# GRBL-Teknic.net
KiCad netlist of a schematic drawn in EAGLE
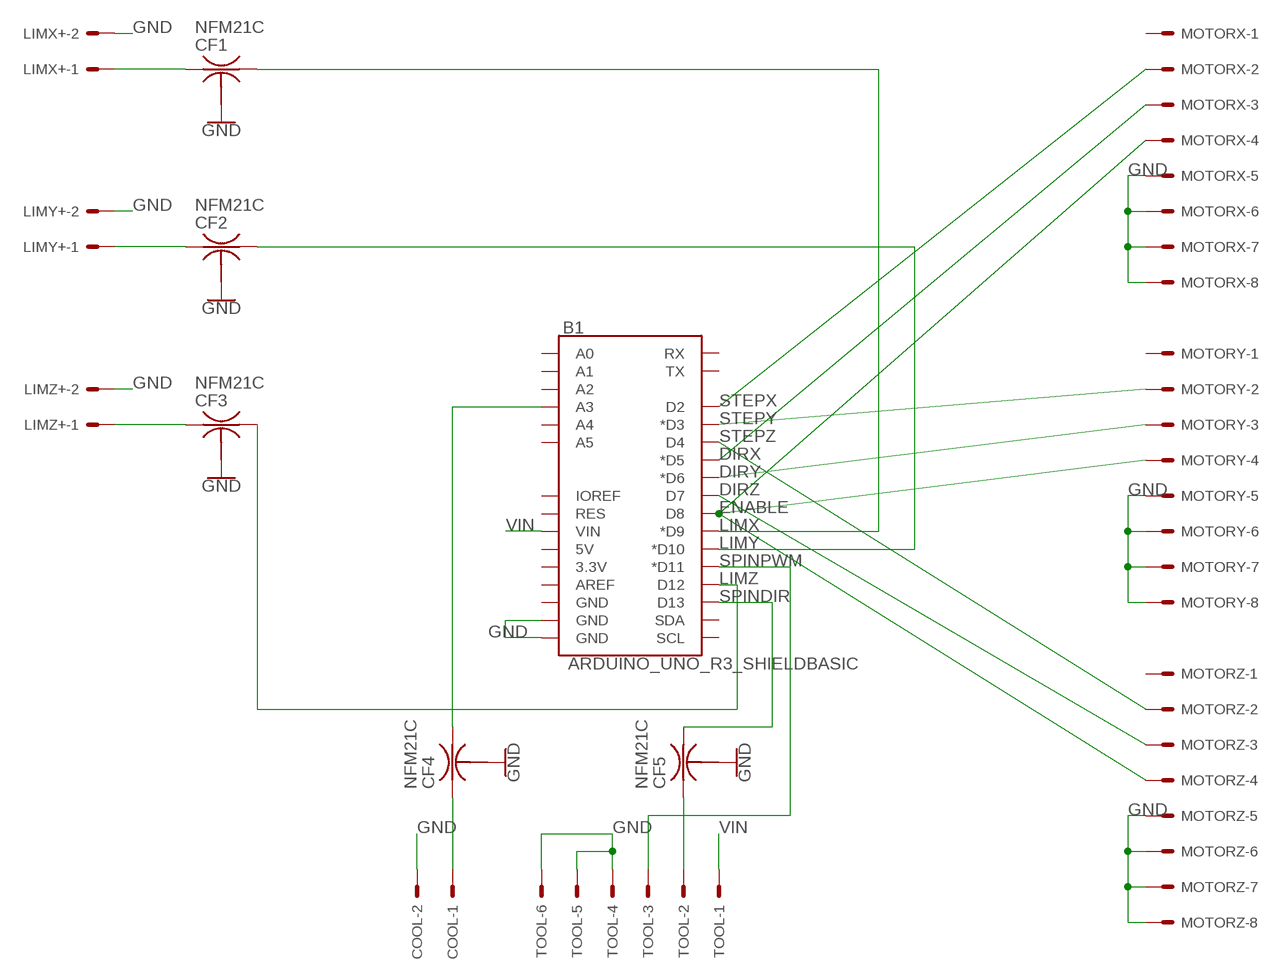
[diagram p0: schematic, sheet 1]

(export (version "E")
  (design (tool "Eeschema 10.0.6"))
  (components
    (comp (ref "B1")
      (value "ARDUINO_UNO_R3_SHIELDBASIC")
      (footprint "eagle-import:UNO_R3_SHIELD")
      (libsource (lib "eagle-import") (part "ARDUINO_UNO_R3_SHIELDBASIC"))
    )
    (comp (ref "CF1")
      (value "NFM21C")
      (footprint "eagle-import:NFM21C")
      (fields (field (name "MPN") "NFM21CC102R1H3D"))
      (libsource (lib "eagle-import") (part "NFM21C"))
    )
    (comp (ref "CF2")
      (value "NFM21C")
      (footprint "eagle-import:NFM21C")
      (fields (field (name "MPN") "NFM21CC102R1H3D"))
      (libsource (lib "eagle-import") (part "NFM21C"))
    )
    (comp (ref "CF3")
      (value "NFM21C")
      (footprint "eagle-import:NFM21C")
      (fields (field (name "MPN") "NFM21CC102R1H3D"))
      (libsource (lib "eagle-import") (part "NFM21C"))
    )
    (comp (ref "CF4")
      (value "NFM21C")
      (footprint "eagle-import:NFM21C")
      (fields (field (name "MPN") "NFM21CC102R1H3D"))
      (libsource (lib "eagle-import") (part "NFM21C"))
    )
    (comp (ref "CF5")
      (value "NFM21C")
      (footprint "eagle-import:NFM21C")
      (fields (field (name "MPN") "NFM21CC102R1H3D"))
      (libsource (lib "eagle-import") (part "NFM21C"))
    )
    (comp (ref "COOL")
      (value "555X-2V")
      (footprint "eagle-import:5566-2")
      (libsource (lib "eagle-import") (part "555X-2V"))
    )
    (comp (ref "LIMX+")
      (value "555X-2V")
      (footprint "eagle-import:5566-2")
      (libsource (lib "eagle-import") (part "555X-2V"))
    )
    (comp (ref "LIMY+")
      (value "555X-2V")
      (footprint "eagle-import:5566-2")
      (libsource (lib "eagle-import") (part "555X-2V"))
    )
    (comp (ref "LIMZ+")
      (value "555X-2V")
      (footprint "eagle-import:5566-2")
      (libsource (lib "eagle-import") (part "555X-2V"))
    )
    (comp (ref "MOTORX")
      (value "555X-8V")
      (footprint "eagle-import:5566-8")
      (libsource (lib "eagle-import") (part "555X-8V"))
    )
    (comp (ref "MOTORY")
      (value "555X-8V")
      (footprint "eagle-import:5566-8")
      (libsource (lib "eagle-import") (part "555X-8V"))
    )
    (comp (ref "MOTORZ")
      (value "555X-8V")
      (footprint "eagle-import:5566-8")
      (libsource (lib "eagle-import") (part "555X-8V"))
    )
    (comp (ref "TOOL")
      (value "555X-6V")
      (footprint "eagle-import:5566-6")
      (libsource (lib "eagle-import") (part "555X-6V"))
    )
  )
  (nets
    (net (code "1") (name "/DIRX") (class "Default")
      (node (ref "B1") (pin "D5") (pinfunction "*D5_D5") (pintype "bidirectional"))
      (node (ref "MOTORX") (pin "3") (pinfunction "S_3") (pintype "passive"))
    )
    (net (code "2") (name "/DIRY") (class "Default")
      (node (ref "B1") (pin "D6") (pinfunction "*D6_D6") (pintype "bidirectional"))
      (node (ref "MOTORY") (pin "3") (pinfunction "S_3") (pintype "passive"))
    )
    (net (code "3") (name "/DIRZ") (class "Default")
      (node (ref "B1") (pin "D7") (pinfunction "D7_D7") (pintype "bidirectional"))
      (node (ref "MOTORZ") (pin "3") (pinfunction "S_3") (pintype "passive"))
    )
    (net (code "4") (name "/ENABLE") (class "Default")
      (node (ref "B1") (pin "D8") (pinfunction "D8_D8") (pintype "bidirectional"))
      (node (ref "MOTORX") (pin "4") (pinfunction "S_4") (pintype "passive"))
      (node (ref "MOTORY") (pin "4") (pinfunction "S_4") (pintype "passive"))
      (node (ref "MOTORZ") (pin "4") (pinfunction "S_4") (pintype "passive"))
    )
    (net (code "5") (name "/LIMX") (class "Default")
      (node (ref "B1") (pin "D9") (pinfunction "*D9_D9") (pintype "bidirectional"))
      (node (ref "CF1") (pin "3") (pinfunction "3_3") (pintype "passive"))
    )
    (net (code "6") (name "/LIMY") (class "Default")
      (node (ref "B1") (pin "D10") (pinfunction "*D10_D10") (pintype "bidirectional"))
      (node (ref "CF2") (pin "3") (pinfunction "3_3") (pintype "passive"))
    )
    (net (code "7") (name "/LIMZ") (class "Default")
      (node (ref "B1") (pin "D12") (pinfunction "D12_D12") (pintype "bidirectional"))
      (node (ref "CF3") (pin "3") (pinfunction "3_3") (pintype "passive"))
    )
    (net (code "8") (name "/SPINDIR") (class "Default")
      (node (ref "B1") (pin "D13") (pinfunction "D13_D13") (pintype "bidirectional"))
      (node (ref "CF5") (pin "3") (pinfunction "3_3") (pintype "passive"))
    )
    (net (code "9") (name "/SPINPWM") (class "Default")
      (node (ref "B1") (pin "D11") (pinfunction "*D11_D11") (pintype "bidirectional"))
      (node (ref "TOOL") (pin "3") (pinfunction "S_3") (pintype "passive"))
    )
    (net (code "10") (name "/STEPX") (class "Default")
      (node (ref "B1") (pin "D2") (pinfunction "D2_D2") (pintype "bidirectional"))
      (node (ref "MOTORX") (pin "2") (pinfunction "S_2") (pintype "passive"))
    )
    (net (code "11") (name "/STEPY") (class "Default")
      (node (ref "B1") (pin "D3") (pinfunction "*D3_D3") (pintype "bidirectional"))
      (node (ref "MOTORY") (pin "2") (pinfunction "S_2") (pintype "passive"))
    )
    (net (code "12") (name "/STEPZ") (class "Default")
      (node (ref "B1") (pin "D4") (pinfunction "D4_D4") (pintype "bidirectional"))
      (node (ref "MOTORZ") (pin "2") (pinfunction "S_2") (pintype "passive"))
    )
    (net (code "13") (name "/VIN") (class "Default")
      (node (ref "B1") (pin "VIN") (pinfunction "VIN_VIN") (pintype "bidirectional"))
      (node (ref "TOOL") (pin "1") (pinfunction "S_1") (pintype "passive"))
    )
    (net (code "14") (name "GND") (class "Default")
      (node (ref "B1") (pin "GND@0") (pinfunction "GND_GND@0") (pintype "bidirectional"))
      (node (ref "B1") (pin "GND@1") (pinfunction "GND_GND@1") (pintype "bidirectional"))
      (node (ref "CF1") (pin "2@1") (pinfunction "2_2@1") (pintype "passive"))
      (node (ref "CF2") (pin "2@1") (pinfunction "2_2@1") (pintype "passive"))
      (node (ref "CF3") (pin "2@1") (pinfunction "2_2@1") (pintype "passive"))
      (node (ref "CF4") (pin "2@1") (pinfunction "2_2@1") (pintype "passive"))
      (node (ref "CF5") (pin "2@1") (pinfunction "2_2@1") (pintype "passive"))
      (node (ref "COOL") (pin "2") (pinfunction "S_2") (pintype "passive"))
      (node (ref "LIMX+") (pin "2") (pinfunction "S_2") (pintype "passive"))
      (node (ref "LIMY+") (pin "2") (pinfunction "S_2") (pintype "passive"))
      (node (ref "LIMZ+") (pin "2") (pinfunction "S_2") (pintype "passive"))
      (node (ref "MOTORX") (pin "5") (pinfunction "S_5") (pintype "passive"))
      (node (ref "MOTORX") (pin "6") (pinfunction "S_6") (pintype "passive"))
      (node (ref "MOTORX") (pin "7") (pinfunction "S_7") (pintype "passive"))
      (node (ref "MOTORX") (pin "8") (pinfunction "S_8") (pintype "passive"))
      (node (ref "MOTORY") (pin "5") (pinfunction "S_5") (pintype "passive"))
      (node (ref "MOTORY") (pin "6") (pinfunction "S_6") (pintype "passive"))
      (node (ref "MOTORY") (pin "7") (pinfunction "S_7") (pintype "passive"))
      (node (ref "MOTORY") (pin "8") (pinfunction "S_8") (pintype "passive"))
      (node (ref "MOTORZ") (pin "5") (pinfunction "S_5") (pintype "passive"))
      (node (ref "MOTORZ") (pin "6") (pinfunction "S_6") (pintype "passive"))
      (node (ref "MOTORZ") (pin "7") (pinfunction "S_7") (pintype "passive"))
      (node (ref "MOTORZ") (pin "8") (pinfunction "S_8") (pintype "passive"))
      (node (ref "TOOL") (pin "4") (pinfunction "S_4") (pintype "passive"))
      (node (ref "TOOL") (pin "5") (pinfunction "S_5") (pintype "passive"))
      (node (ref "TOOL") (pin "6") (pinfunction "S_6") (pintype "passive"))
    )
    (net (code "15") (name "Net-(B1-PadA3)") (class "Default")
      (node (ref "B1") (pin "A3") (pinfunction "A3_A3") (pintype "bidirectional"))
      (node (ref "CF4") (pin "3") (pinfunction "3_3") (pintype "passive"))
    )
    (net (code "16") (name "Net-(COOLA-S)") (class "Default")
      (node (ref "CF4") (pin "1") (pinfunction "1_1") (pintype "passive"))
      (node (ref "COOL") (pin "1") (pinfunction "S_1") (pintype "passive"))
    )
    (net (code "17") (name "Net-(LIMX+A-S)") (class "Default")
      (node (ref "CF1") (pin "1") (pinfunction "1_1") (pintype "passive"))
      (node (ref "LIMX+") (pin "1") (pinfunction "S_1") (pintype "passive"))
    )
    (net (code "18") (name "Net-(LIMY+A-S)") (class "Default")
      (node (ref "CF2") (pin "1") (pinfunction "1_1") (pintype "passive"))
      (node (ref "LIMY+") (pin "1") (pinfunction "S_1") (pintype "passive"))
    )
    (net (code "19") (name "Net-(LIMZ+A-S)") (class "Default")
      (node (ref "CF3") (pin "1") (pinfunction "1_1") (pintype "passive"))
      (node (ref "LIMZ+") (pin "1") (pinfunction "S_1") (pintype "passive"))
    )
    (net (code "20") (name "Net-(TOOLB-S)") (class "Default")
      (node (ref "CF5") (pin "1") (pinfunction "1_1") (pintype "passive"))
      (node (ref "TOOL") (pin "2") (pinfunction "S_2") (pintype "passive"))
    )
    (net (code "21") (name "unconnected-(B1-GND-PadGND@2)") (class "Default")
      (node (ref "B1") (pin "GND@2") (pinfunction "GND_GND@2") (pintype "bidirectional"))
    )
    (net (code "22") (name "unconnected-(B1-Pad3.3V)") (class "Default")
      (node (ref "B1") (pin "3.3V") (pinfunction "3.3V_3.3V") (pintype "bidirectional"))
    )
    (net (code "23") (name "unconnected-(B1-Pad5V)") (class "Default")
      (node (ref "B1") (pin "5V") (pinfunction "5V_5V") (pintype "bidirectional"))
    )
    (net (code "24") (name "unconnected-(B1-PadA0)") (class "Default")
      (node (ref "B1") (pin "A0") (pinfunction "A0_A0") (pintype "bidirectional"))
    )
    (net (code "25") (name "unconnected-(B1-PadA1)") (class "Default")
      (node (ref "B1") (pin "A1") (pinfunction "A1_A1") (pintype "bidirectional"))
    )
    (net (code "26") (name "unconnected-(B1-PadA2)") (class "Default")
      (node (ref "B1") (pin "A2") (pinfunction "A2_A2") (pintype "bidirectional"))
    )
    (net (code "27") (name "unconnected-(B1-PadA4)") (class "Default")
      (node (ref "B1") (pin "A4") (pinfunction "A4_A4") (pintype "bidirectional"))
    )
    (net (code "28") (name "unconnected-(B1-PadA5)") (class "Default")
      (node (ref "B1") (pin "A5") (pinfunction "A5_A5") (pintype "bidirectional"))
    )
    (net (code "29") (name "unconnected-(B1-PadAREF)") (class "Default")
      (node (ref "B1") (pin "AREF") (pinfunction "AREF_AREF") (pintype "bidirectional"))
    )
    (net (code "30") (name "unconnected-(B1-PadIOREF)") (class "Default")
      (node (ref "B1") (pin "IOREF") (pinfunction "IOREF_IOREF") (pintype "bidirectional"))
    )
    (net (code "31") (name "unconnected-(B1-PadRES)") (class "Default")
      (node (ref "B1") (pin "RES") (pinfunction "RES_RES") (pintype "bidirectional"))
    )
    (net (code "32") (name "unconnected-(B1-PadRX)") (class "Default")
      (node (ref "B1") (pin "RX") (pinfunction "RX_RX") (pintype "bidirectional"))
    )
    (net (code "33") (name "unconnected-(B1-PadSCL)") (class "Default")
      (node (ref "B1") (pin "SCL") (pinfunction "SCL_SCL") (pintype "bidirectional"))
    )
    (net (code "34") (name "unconnected-(B1-PadSDA)") (class "Default")
      (node (ref "B1") (pin "SDA") (pinfunction "SDA_SDA") (pintype "bidirectional"))
    )
    (net (code "35") (name "unconnected-(B1-PadTX)") (class "Default")
      (node (ref "B1") (pin "TX") (pinfunction "TX_TX") (pintype "bidirectional"))
    )
    (net (code "36") (name "unconnected-(CF1-2-Pad2@2)") (class "Default")
      (node (ref "CF1") (pin "2@2") (pinfunction "2_2@2") (pintype "passive"))
    )
    (net (code "37") (name "unconnected-(CF2-2-Pad2@2)") (class "Default")
      (node (ref "CF2") (pin "2@2") (pinfunction "2_2@2") (pintype "passive"))
    )
    (net (code "38") (name "unconnected-(CF3-2-Pad2@2)") (class "Default")
      (node (ref "CF3") (pin "2@2") (pinfunction "2_2@2") (pintype "passive"))
    )
    (net (code "39") (name "unconnected-(CF4-2-Pad2@2)") (class "Default")
      (node (ref "CF4") (pin "2@2") (pinfunction "2_2@2") (pintype "passive"))
    )
    (net (code "40") (name "unconnected-(CF5-2-Pad2@2)") (class "Default")
      (node (ref "CF5") (pin "2@2") (pinfunction "2_2@2") (pintype "passive"))
    )
    (net (code "41") (name "unconnected-(MOTORXA-S-Pad1)") (class "Default")
      (node (ref "MOTORX") (pin "1") (pinfunction "S_1") (pintype "passive"))
    )
    (net (code "42") (name "unconnected-(MOTORYA-S-Pad1)") (class "Default")
      (node (ref "MOTORY") (pin "1") (pinfunction "S_1") (pintype "passive"))
    )
    (net (code "43") (name "unconnected-(MOTORZA-S-Pad1)") (class "Default")
      (node (ref "MOTORZ") (pin "1") (pinfunction "S_1") (pintype "passive"))
    )
  )
)
